# Digital.net
KiCad netlist of a schematic drawn in Altium Designer
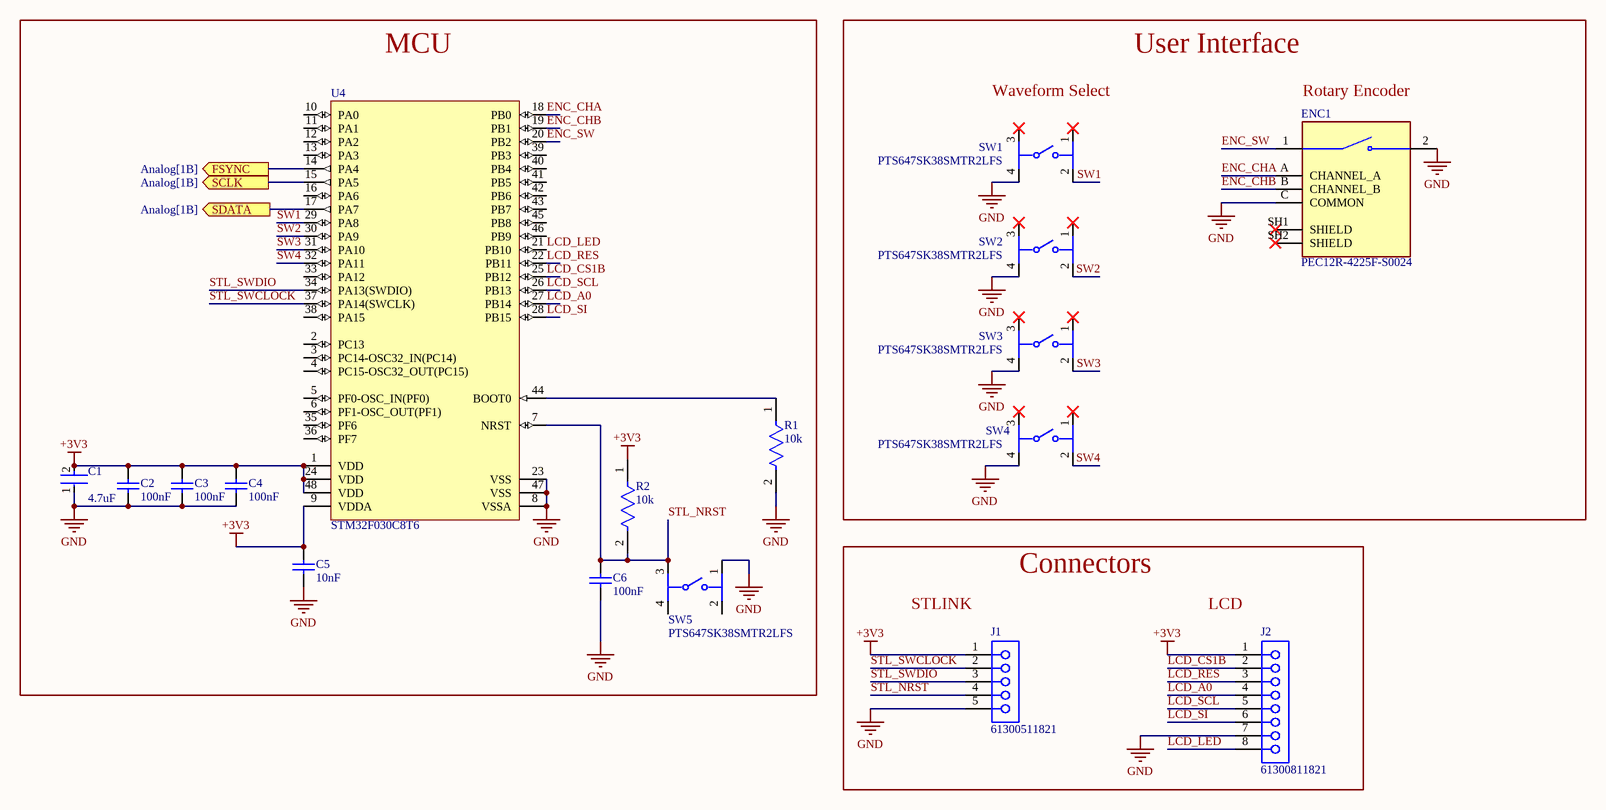
[diagram p0: Digital.SchDoc]

(export (version "E")
  (design (tool "Eeschema 10.0.6"))
  (components
    (comp (ref "C1")
      (value "4.7uF")
      (footprint "FP-GRM219-0_15-0_1-IPC_B")
      (description "Chip Multilayer Ceramic Capacitors for General Purpose, 0805, 4.7uF, X5R, 15%, 20%, 25V")
      (libsource (lib "Altium Content Vault") (part "236180d848d6139a670b325ea6854c9"))
    )
    (comp (ref "C2")
      (value "100nF")
      (footprint "CAPC1608X87X45LL20T05")
      (description "Ceramic 100nF X7R 16V 5%")
      (fields (field (name "PART NUMBER") "C0603X104J4RACTU") (field (name "MANUFACTURER") "Kemet"))
      (libsource (lib "Altium Content Vault") (part "CAP"))
    )
    (comp (ref "C3")
      (value "100nF")
      (footprint "CAPC1608X87X45LL20T05")
      (description "Ceramic 100nF X7R 16V 5%")
      (fields (field (name "PART NUMBER") "C0603X104J4RACTU") (field (name "MANUFACTURER") "Kemet"))
      (libsource (lib "Altium Content Vault") (part "CAP"))
    )
    (comp (ref "C4")
      (value "100nF")
      (footprint "CAPC1608X87X45LL20T05")
      (description "Ceramic 100nF X7R 16V 5%")
      (fields (field (name "PART NUMBER") "C0603X104J4RACTU") (field (name "MANUFACTURER") "Kemet"))
      (libsource (lib "Altium Content Vault") (part "CAP"))
    )
    (comp (ref "C5")
      (value "10nF")
      (footprint "CAPC1206(3216)150_L")
      (description "CAP 10nF 10V ±5% 1206 (3216 Metric) Thickness 1.45mm SMD")
      (fields (field (name "TOLERANCE") "Â±5%"))
      (libsource (lib "Altium Content Vault") (part "CAP"))
    )
    (comp (ref "C6")
      (value "100nF")
      (footprint "CAPC1608X87X45LL20T05")
      (description "Ceramic 100nF X7R 16V 5%")
      (fields (field (name "PART NUMBER") "C0603X104J4RACTU") (field (name "MANUFACTURER") "Kemet"))
      (libsource (lib "Altium Content Vault") (part "CAP"))
    )
    (comp (ref "ENC1")
      (value "PEC12R-4225F-S0024")
      (footprint "XDCR_PEC12R-4225F-S0024")
      (fields (field (name "MF") "Bourns"))
      (libsource (lib "PEC12R-4225F-S0024") (part "PEC12R-4225F-S0024"))
    )
    (comp (ref "J1")
      (value "61300511821")
      (footprint "61300511821")
      (libsource (lib "Altium Content Vault") (part "Header_Female_1R_05P"))
    )
    (comp (ref "J2")
      (value "61300811821")
      (footprint "61300811821")
      (libsource (lib "Altium Content Vault") (part "Header_Female_1R_08P"))
    )
    (comp (ref "R1")
      (value "10k")
      (footprint "FP-TFCR0402-IPC_B")
      (description "RES Thin Film,  10kΩ, 0.1%, 0.063W, 50ppm/°C, 0402")
      (libsource (lib "Altium Content Vault") (part "1029c3af85768c4190bb7ad29bc67b5"))
    )
    (comp (ref "R2")
      (value "10k")
      (footprint "FP-TFCR0402-IPC_B")
      (description "RES Thin Film,  10kΩ, 0.1%, 0.063W, 50ppm/°C, 0402")
      (libsource (lib "Altium Content Vault") (part "1029c3af85768c4190bb7ad29bc67b5"))
    )
    (comp (ref "SW1")
      (value "PTS647SK38SMTR2LFS")
      (footprint "FP-PTS647SK38SMTR2LFS-MFG")
      (description "TACT 4.5 X 4.5, 3.8 MM H, 2.5N,")
      (libsource (lib "Altium Content Vault") (part "1adf0dd01260c80cf25a44bfd6b99ba"))
    )
    (comp (ref "SW2")
      (value "PTS647SK38SMTR2LFS")
      (footprint "FP-PTS647SK38SMTR2LFS-MFG")
      (description "TACT 4.5 X 4.5, 3.8 MM H, 2.5N,")
      (libsource (lib "Altium Content Vault") (part "1adf0dd01260c80cf25a44bfd6b99ba"))
    )
    (comp (ref "SW3")
      (value "PTS647SK38SMTR2LFS")
      (footprint "FP-PTS647SK38SMTR2LFS-MFG")
      (description "TACT 4.5 X 4.5, 3.8 MM H, 2.5N,")
      (libsource (lib "Altium Content Vault") (part "1adf0dd01260c80cf25a44bfd6b99ba"))
    )
    (comp (ref "SW4")
      (value "PTS647SK38SMTR2LFS")
      (footprint "FP-PTS647SK38SMTR2LFS-MFG")
      (description "TACT 4.5 X 4.5, 3.8 MM H, 2.5N,")
      (libsource (lib "Altium Content Vault") (part "1adf0dd01260c80cf25a44bfd6b99ba"))
    )
    (comp (ref "SW5")
      (value "PTS647SK38SMTR2LFS")
      (footprint "FP-PTS647SK38SMTR2LFS-MFG")
      (description "TACT 4.5 X 4.5, 3.8 MM H, 2.5N,")
      (libsource (lib "Altium Content Vault") (part "1adf0dd01260c80cf25a44bfd6b99ba"))
    )
    (comp (ref "U4")
      (value "STM32F030C8T6")
      (footprint "STM-LQFP48_M")
      (fields
        (field (name "MANUFACTURER") "STMicroelectronics")
        (field (name "PARTNUMBER") "STM32F030C8T6TR")
      )
      (libsource (lib "Altium Content Vault") (part "MC-ARM-STM32F030-LQFP48_A"))
    )
  )
  (nets
    (net (code "1") (name "+3V3") (class "Default")
      (node (ref "C1") (pin "2") (pinfunction "2_2") (pintype "passive"))
      (node (ref "C2") (pin "2") (pinfunction "2_2") (pintype "passive"))
      (node (ref "C3") (pin "2") (pinfunction "2_2") (pintype "passive"))
      (node (ref "C4") (pin "2") (pinfunction "2_2") (pintype "passive"))
      (node (ref "C5") (pin "2") (pinfunction "2_2") (pintype "passive"))
      (node (ref "J1") (pin "1") (pinfunction "1_1") (pintype "passive"))
      (node (ref "J2") (pin "1") (pinfunction "1_1") (pintype "passive"))
      (node (ref "R2") (pin "1") (pinfunction "1_1") (pintype "passive"))
      (node (ref "U4") (pin "1") (pinfunction "VDD_1") (pintype "power_in"))
      (node (ref "U4") (pin "24") (pinfunction "VDD_24") (pintype "power_in"))
      (node (ref "U4") (pin "48") (pinfunction "VDD_48") (pintype "power_in"))
      (node (ref "U4") (pin "9") (pinfunction "VDDA_9") (pintype "power_in"))
    )
    (net (code "2") (name "/ENC_CHA") (class "Default")
      (node (ref "ENC1") (pin "A") (pinfunction "CHANNEL_A_A") (pintype "passive"))
      (node (ref "U4") (pin "18") (pinfunction "PB0_18") (pintype "bidirectional"))
    )
    (net (code "3") (name "/ENC_CHB") (class "Default")
      (node (ref "ENC1") (pin "B") (pinfunction "CHANNEL_B_B") (pintype "passive"))
      (node (ref "U4") (pin "19") (pinfunction "PB1_19") (pintype "bidirectional"))
    )
    (net (code "4") (name "/ENC_SW") (class "Default")
      (node (ref "ENC1") (pin "1") (pinfunction "1_1") (pintype "passive"))
      (node (ref "U4") (pin "20") (pinfunction "PB2_20") (pintype "bidirectional"))
    )
    (net (code "5") (name "/FSYNC") (class "Default")
      (node (ref "U4") (pin "14") (pinfunction "PA4_14") (pintype "output"))
    )
    (net (code "6") (name "/LCD_A0") (class "Default")
      (node (ref "J2") (pin "4") (pinfunction "4_4") (pintype "passive"))
      (node (ref "U4") (pin "27") (pinfunction "PB14_27") (pintype "bidirectional"))
    )
    (net (code "7") (name "/LCD_CS1B") (class "Default")
      (node (ref "J2") (pin "2") (pinfunction "2_2") (pintype "passive"))
      (node (ref "U4") (pin "25") (pinfunction "PB12_25") (pintype "bidirectional"))
    )
    (net (code "8") (name "/LCD_LED") (class "Default")
      (node (ref "J2") (pin "8") (pinfunction "8_8") (pintype "passive"))
      (node (ref "U4") (pin "21") (pinfunction "PB10_21") (pintype "bidirectional"))
    )
    (net (code "9") (name "/LCD_RES") (class "Default")
      (node (ref "J2") (pin "3") (pinfunction "3_3") (pintype "passive"))
      (node (ref "U4") (pin "22") (pinfunction "PB11_22") (pintype "bidirectional"))
    )
    (net (code "10") (name "/LCD_SCL") (class "Default")
      (node (ref "J2") (pin "5") (pinfunction "5_5") (pintype "passive"))
      (node (ref "U4") (pin "26") (pinfunction "PB13_26") (pintype "bidirectional"))
    )
    (net (code "11") (name "/LCD_SI") (class "Default")
      (node (ref "J2") (pin "6") (pinfunction "6_6") (pintype "passive"))
      (node (ref "U4") (pin "28") (pinfunction "PB15_28") (pintype "bidirectional"))
    )
    (net (code "12") (name "/SCLK") (class "Default")
      (node (ref "U4") (pin "15") (pinfunction "PA5_15") (pintype "output"))
    )
    (net (code "13") (name "/SDATA") (class "Default")
      (node (ref "U4") (pin "17") (pinfunction "PA7_17") (pintype "output"))
    )
    (net (code "14") (name "/STL_NRST") (class "Default")
      (node (ref "C6") (pin "2") (pinfunction "2_2") (pintype "passive"))
      (node (ref "J1") (pin "4") (pinfunction "4_4") (pintype "passive"))
      (node (ref "R2") (pin "2") (pinfunction "2_2") (pintype "passive"))
      (node (ref "SW5") (pin "3") (pinfunction "3_3") (pintype "passive"))
      (node (ref "U4") (pin "7") (pinfunction "NRST_7") (pintype "bidirectional"))
    )
    (net (code "15") (name "/STL_SWCLOCK") (class "Default")
      (node (ref "J1") (pin "2") (pinfunction "2_2") (pintype "passive"))
      (node (ref "U4") (pin "37") (pinfunction "PA14(SWCLK)_37") (pintype "bidirectional"))
    )
    (net (code "16") (name "/STL_SWDIO") (class "Default")
      (node (ref "J1") (pin "3") (pinfunction "3_3") (pintype "passive"))
      (node (ref "U4") (pin "34") (pinfunction "PA13(SWDIO)_34") (pintype "bidirectional"))
    )
    (net (code "17") (name "/SW1") (class "Default")
      (node (ref "SW1") (pin "2") (pinfunction "2_2") (pintype "passive"))
      (node (ref "U4") (pin "29") (pinfunction "PA8_29") (pintype "bidirectional"))
    )
    (net (code "18") (name "/SW2") (class "Default")
      (node (ref "SW2") (pin "2") (pinfunction "2_2") (pintype "passive"))
      (node (ref "U4") (pin "30") (pinfunction "PA9_30") (pintype "bidirectional"))
    )
    (net (code "19") (name "/SW3") (class "Default")
      (node (ref "SW3") (pin "2") (pinfunction "2_2") (pintype "passive"))
      (node (ref "U4") (pin "31") (pinfunction "PA10_31") (pintype "bidirectional"))
    )
    (net (code "20") (name "/SW4") (class "Default")
      (node (ref "SW4") (pin "2") (pinfunction "2_2") (pintype "passive"))
      (node (ref "U4") (pin "32") (pinfunction "PA11_32") (pintype "bidirectional"))
    )
    (net (code "21") (name "GND") (class "Default")
      (node (ref "C1") (pin "1") (pinfunction "1_1") (pintype "passive"))
      (node (ref "C2") (pin "1") (pinfunction "1_1") (pintype "passive"))
      (node (ref "C3") (pin "1") (pinfunction "1_1") (pintype "passive"))
      (node (ref "C4") (pin "1") (pinfunction "1_1") (pintype "passive"))
      (node (ref "C5") (pin "1") (pinfunction "1_1") (pintype "passive"))
      (node (ref "C6") (pin "1") (pinfunction "1_1") (pintype "passive"))
      (node (ref "ENC1") (pin "2") (pinfunction "2_2") (pintype "passive"))
      (node (ref "ENC1") (pin "C") (pinfunction "COMMON_C") (pintype "passive"))
      (node (ref "J1") (pin "5") (pinfunction "5_5") (pintype "passive"))
      (node (ref "J2") (pin "7") (pinfunction "7_7") (pintype "passive"))
      (node (ref "R1") (pin "2") (pinfunction "2_2") (pintype "passive"))
      (node (ref "SW1") (pin "4") (pinfunction "4_4") (pintype "passive"))
      (node (ref "SW2") (pin "4") (pinfunction "4_4") (pintype "passive"))
      (node (ref "SW3") (pin "4") (pinfunction "4_4") (pintype "passive"))
      (node (ref "SW4") (pin "4") (pinfunction "4_4") (pintype "passive"))
      (node (ref "SW5") (pin "1") (pinfunction "1_1") (pintype "passive"))
      (node (ref "U4") (pin "23") (pinfunction "VSS_23") (pintype "power_in"))
      (node (ref "U4") (pin "47") (pinfunction "VSS_47") (pintype "power_in"))
      (node (ref "U4") (pin "8") (pinfunction "VSSA_8") (pintype "power_in"))
    )
    (net (code "22") (name "Net-(U4-BOOT0)") (class "Default")
      (node (ref "R1") (pin "1") (pinfunction "1_1") (pintype "passive"))
      (node (ref "U4") (pin "44") (pinfunction "BOOT0_44") (pintype "input"))
    )
    (net (code "23") (name "unconnected-(ENC1-SHIELD-PadSH1)") (class "Default")
      (node (ref "ENC1") (pin "SH1") (pinfunction "SHIELD_SH1") (pintype "passive+no_connect"))
    )
    (net (code "24") (name "unconnected-(ENC1-SHIELD-PadSH2)") (class "Default")
      (node (ref "ENC1") (pin "SH2") (pinfunction "SHIELD_SH2") (pintype "passive+no_connect"))
    )
    (net (code "25") (name "unconnected-(SW1-Pad1)") (class "Default")
      (node (ref "SW1") (pin "1") (pinfunction "1_1") (pintype "passive+no_connect"))
    )
    (net (code "26") (name "unconnected-(SW1-Pad3)") (class "Default")
      (node (ref "SW1") (pin "3") (pinfunction "3_3") (pintype "passive+no_connect"))
    )
    (net (code "27") (name "unconnected-(SW2-Pad1)") (class "Default")
      (node (ref "SW2") (pin "1") (pinfunction "1_1") (pintype "passive+no_connect"))
    )
    (net (code "28") (name "unconnected-(SW2-Pad3)") (class "Default")
      (node (ref "SW2") (pin "3") (pinfunction "3_3") (pintype "passive+no_connect"))
    )
    (net (code "29") (name "unconnected-(SW3-Pad1)") (class "Default")
      (node (ref "SW3") (pin "1") (pinfunction "1_1") (pintype "passive+no_connect"))
    )
    (net (code "30") (name "unconnected-(SW3-Pad3)") (class "Default")
      (node (ref "SW3") (pin "3") (pinfunction "3_3") (pintype "passive+no_connect"))
    )
    (net (code "31") (name "unconnected-(SW4-Pad1)") (class "Default")
      (node (ref "SW4") (pin "1") (pinfunction "1_1") (pintype "passive+no_connect"))
    )
    (net (code "32") (name "unconnected-(SW4-Pad3)") (class "Default")
      (node (ref "SW4") (pin "3") (pinfunction "3_3") (pintype "passive+no_connect"))
    )
    (net (code "33") (name "unconnected-(SW5-Pad2)") (class "Default")
      (node (ref "SW5") (pin "2") (pinfunction "2_2") (pintype "passive"))
    )
    (net (code "34") (name "unconnected-(SW5-Pad4)") (class "Default")
      (node (ref "SW5") (pin "4") (pinfunction "4_4") (pintype "passive"))
    )
    (net (code "35") (name "unconnected-(U4-PA0-Pad10)") (class "Default")
      (node (ref "U4") (pin "10") (pinfunction "PA0_10") (pintype "bidirectional"))
    )
    (net (code "36") (name "unconnected-(U4-PA1-Pad11)") (class "Default")
      (node (ref "U4") (pin "11") (pinfunction "PA1_11") (pintype "bidirectional"))
    )
    (net (code "37") (name "unconnected-(U4-PA2-Pad12)") (class "Default")
      (node (ref "U4") (pin "12") (pinfunction "PA2_12") (pintype "bidirectional"))
    )
    (net (code "38") (name "unconnected-(U4-PA3-Pad13)") (class "Default")
      (node (ref "U4") (pin "13") (pinfunction "PA3_13") (pintype "bidirectional"))
    )
    (net (code "39") (name "unconnected-(U4-PA6-Pad16)") (class "Default")
      (node (ref "U4") (pin "16") (pinfunction "PA6_16") (pintype "bidirectional"))
    )
    (net (code "40") (name "unconnected-(U4-PA12-Pad33)") (class "Default")
      (node (ref "U4") (pin "33") (pinfunction "PA12_33") (pintype "bidirectional"))
    )
    (net (code "41") (name "unconnected-(U4-PA15-Pad38)") (class "Default")
      (node (ref "U4") (pin "38") (pinfunction "PA15_38") (pintype "bidirectional"))
    )
    (net (code "42") (name "unconnected-(U4-PB3-Pad39)") (class "Default")
      (node (ref "U4") (pin "39") (pinfunction "PB3_39") (pintype "bidirectional"))
    )
    (net (code "43") (name "unconnected-(U4-PB4-Pad40)") (class "Default")
      (node (ref "U4") (pin "40") (pinfunction "PB4_40") (pintype "bidirectional"))
    )
    (net (code "44") (name "unconnected-(U4-PB5-Pad41)") (class "Default")
      (node (ref "U4") (pin "41") (pinfunction "PB5_41") (pintype "bidirectional"))
    )
    (net (code "45") (name "unconnected-(U4-PB6-Pad42)") (class "Default")
      (node (ref "U4") (pin "42") (pinfunction "PB6_42") (pintype "bidirectional"))
    )
    (net (code "46") (name "unconnected-(U4-PB7-Pad43)") (class "Default")
      (node (ref "U4") (pin "43") (pinfunction "PB7_43") (pintype "bidirectional"))
    )
    (net (code "47") (name "unconnected-(U4-PB8-Pad45)") (class "Default")
      (node (ref "U4") (pin "45") (pinfunction "PB8_45") (pintype "bidirectional"))
    )
    (net (code "48") (name "unconnected-(U4-PB9-Pad46)") (class "Default")
      (node (ref "U4") (pin "46") (pinfunction "PB9_46") (pintype "bidirectional"))
    )
    (net (code "49") (name "unconnected-(U4-PC13-Pad2)") (class "Default")
      (node (ref "U4") (pin "2") (pinfunction "PC13_2") (pintype "bidirectional"))
    )
    (net (code "50") (name "unconnected-(U4-PC14-OSC32_IN(PC14)-Pad3)") (class "Default")
      (node (ref "U4") (pin "3") (pinfunction "PC14-OSC32_IN(PC14)_3") (pintype "bidirectional"))
    )
    (net (code "51") (name "unconnected-(U4-PC15-OSC32_OUT(PC15)-Pad4)") (class "Default")
      (node (ref "U4") (pin "4") (pinfunction "PC15-OSC32_OUT(PC15)_4") (pintype "bidirectional"))
    )
    (net (code "52") (name "unconnected-(U4-PF0-OSC_IN(PF0)-Pad5)") (class "Default")
      (node (ref "U4") (pin "5") (pinfunction "PF0-OSC_IN(PF0)_5") (pintype "bidirectional"))
    )
    (net (code "53") (name "unconnected-(U4-PF1-OSC_OUT(PF1)-Pad6)") (class "Default")
      (node (ref "U4") (pin "6") (pinfunction "PF1-OSC_OUT(PF1)_6") (pintype "bidirectional"))
    )
    (net (code "54") (name "unconnected-(U4-PF6-Pad35)") (class "Default")
      (node (ref "U4") (pin "35") (pinfunction "PF6_35") (pintype "bidirectional"))
    )
    (net (code "55") (name "unconnected-(U4-PF7-Pad36)") (class "Default")
      (node (ref "U4") (pin "36") (pinfunction "PF7_36") (pintype "bidirectional"))
    )
  )
)
